# OsmoPod3_0.net
KiCad netlist of a schematic drawn in EAGLE
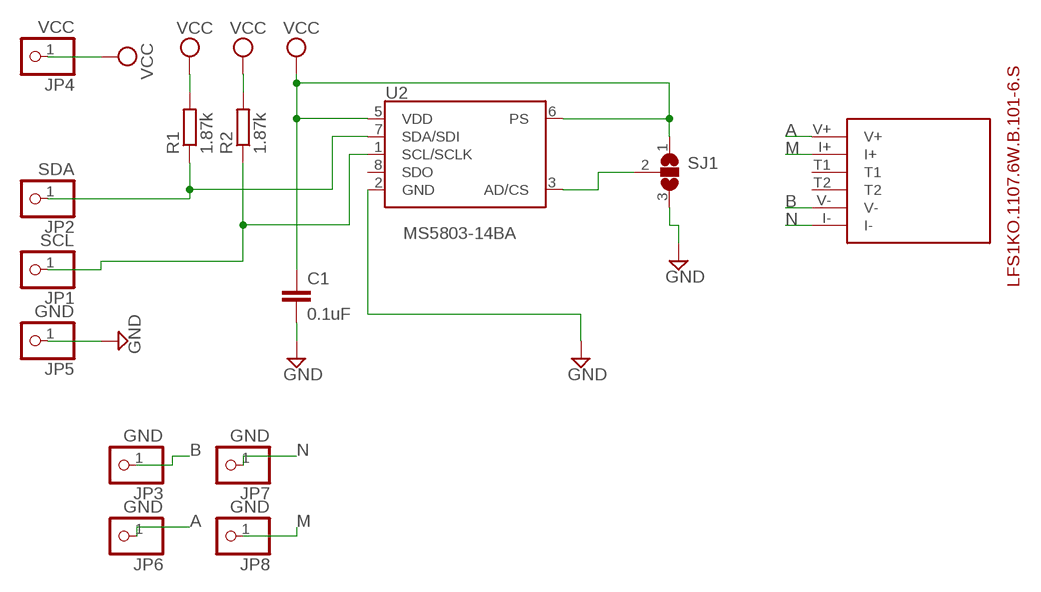
[diagram p0: schematic, sheet 1]

(export (version "E")
  (design (tool "Eeschema 10.0.6"))
  (components
    (comp (ref "C1")
      (value "0.1uF")
      (footprint "eagle-import:C0805")
      (libsource (lib "eagle-import") (part "C-EUC0805"))
    )
    (comp (ref "JP1")
      (value "SCL")
      (footprint "eagle-import:1X01")
      (libsource (lib "eagle-import") (part "PINHD-1X1"))
    )
    (comp (ref "JP2")
      (value "SDA")
      (footprint "eagle-import:1X01")
      (libsource (lib "eagle-import") (part "PINHD-1X1"))
    )
    (comp (ref "JP3")
      (value "GND")
      (footprint "eagle-import:1X01")
      (libsource (lib "eagle-import") (part "PINHD-1X1"))
    )
    (comp (ref "JP4")
      (value "VCC")
      (footprint "eagle-import:1X01")
      (libsource (lib "eagle-import") (part "PINHD-1X1"))
    )
    (comp (ref "JP5")
      (value "GND")
      (footprint "eagle-import:1X01")
      (libsource (lib "eagle-import") (part "PINHD-1X1"))
    )
    (comp (ref "JP6")
      (value "GND")
      (footprint "eagle-import:1X01")
      (libsource (lib "eagle-import") (part "PINHD-1X1"))
    )
    (comp (ref "JP7")
      (value "GND")
      (footprint "eagle-import:1X01")
      (libsource (lib "eagle-import") (part "PINHD-1X1"))
    )
    (comp (ref "JP8")
      (value "GND")
      (footprint "eagle-import:1X01")
      (libsource (lib "eagle-import") (part "PINHD-1X1"))
    )
    (comp (ref "R1")
      (value "1.87k")
      (footprint "eagle-import:R0805")
      (libsource (lib "eagle-import") (part "R-EU_R0805"))
    )
    (comp (ref "R2")
      (value "1.87k")
      (footprint "eagle-import:R0805")
      (libsource (lib "eagle-import") (part "R-EU_R0805"))
    )
    (comp (ref "SJ1")
      (value "SJ2W")
      (footprint "eagle-import:SJ_2")
      (libsource (lib "eagle-import") (part "SJ2W"))
    )
    (comp (ref "U$1")
      (value "LFS1107_6W")
      (footprint "eagle-import:LFS1107_6W")
      (libsource (lib "eagle-import") (part "LFS1107_6W"))
    )
    (comp (ref "U2")
      (value "MS5803-14BA")
      (footprint "eagle-import:MS5803")
      (libsource (lib "eagle-import") (part "MS5803-14BA"))
    )
  )
  (nets
    (net (code "1") (name "/A") (class "Default")
      (node (ref "JP6") (pin "1") (pinfunction "1_1") (pintype "passive"))
      (node (ref "U$1") (pin "V+") (pinfunction "V+_V+") (pintype "bidirectional"))
    )
    (net (code "2") (name "/B") (class "Default")
      (node (ref "JP3") (pin "1") (pinfunction "1_1") (pintype "passive"))
      (node (ref "U$1") (pin "V-") (pinfunction "V-_V-") (pintype "bidirectional"))
    )
    (net (code "3") (name "/M") (class "Default")
      (node (ref "JP8") (pin "1") (pinfunction "1_1") (pintype "passive"))
      (node (ref "U$1") (pin "I+") (pinfunction "I+_I+") (pintype "bidirectional"))
    )
    (net (code "4") (name "/N") (class "Default")
      (node (ref "JP7") (pin "1") (pinfunction "1_1") (pintype "passive"))
      (node (ref "U$1") (pin "I-") (pinfunction "I-_I-") (pintype "bidirectional"))
    )
    (net (code "5") (name "GND") (class "Default")
      (node (ref "C1") (pin "2") (pinfunction "2_2") (pintype "passive"))
      (node (ref "JP5") (pin "1") (pinfunction "1_1") (pintype "passive"))
      (node (ref "SJ1") (pin "3") (pinfunction "3_3") (pintype "passive"))
      (node (ref "U2") (pin "2") (pinfunction "GND_2") (pintype "bidirectional"))
    )
    (net (code "6") (name "Net-(U2-AD{slash}CS)") (class "Default")
      (node (ref "SJ1") (pin "2") (pinfunction "2_2") (pintype "passive"))
      (node (ref "U2") (pin "3") (pinfunction "AD/CS_3") (pintype "bidirectional"))
    )
    (net (code "7") (name "Net-(U2-SCL{slash}SCLK)") (class "Default")
      (node (ref "JP1") (pin "1") (pinfunction "1_1") (pintype "passive"))
      (node (ref "R2") (pin "1") (pinfunction "1_1") (pintype "passive"))
      (node (ref "U2") (pin "1") (pinfunction "SCL/SCLK_1") (pintype "bidirectional"))
    )
    (net (code "8") (name "Net-(U2-SDA{slash}SDI)") (class "Default")
      (node (ref "JP2") (pin "1") (pinfunction "1_1") (pintype "passive"))
      (node (ref "R1") (pin "1") (pinfunction "1_1") (pintype "passive"))
      (node (ref "U2") (pin "7") (pinfunction "SDA/SDI_7") (pintype "bidirectional"))
    )
    (net (code "9") (name "VCC") (class "Default")
      (node (ref "C1") (pin "1") (pinfunction "1_1") (pintype "passive"))
      (node (ref "JP4") (pin "1") (pinfunction "1_1") (pintype "passive"))
      (node (ref "R1") (pin "2") (pinfunction "2_2") (pintype "passive"))
      (node (ref "R2") (pin "2") (pinfunction "2_2") (pintype "passive"))
      (node (ref "SJ1") (pin "1") (pinfunction "1_1") (pintype "passive"))
      (node (ref "U2") (pin "5") (pinfunction "VDD_5") (pintype "bidirectional"))
      (node (ref "U2") (pin "6") (pinfunction "PS_6") (pintype "bidirectional"))
    )
    (net (code "10") (name "unconnected-(U$1-PadT1)") (class "Default")
      (node (ref "U$1") (pin "T1") (pinfunction "T1_T1") (pintype "bidirectional"))
    )
    (net (code "11") (name "unconnected-(U$1-PadT2)") (class "Default")
      (node (ref "U$1") (pin "T2") (pinfunction "T2_T2") (pintype "bidirectional"))
    )
    (net (code "12") (name "unconnected-(U2-SDO-Pad8)") (class "Default")
      (node (ref "U2") (pin "8") (pinfunction "SDO_8") (pintype "bidirectional"))
    )
  )
)
